# Ana-DigiColorMixerV1.net
KiCad netlist of a schematic drawn in EAGLE
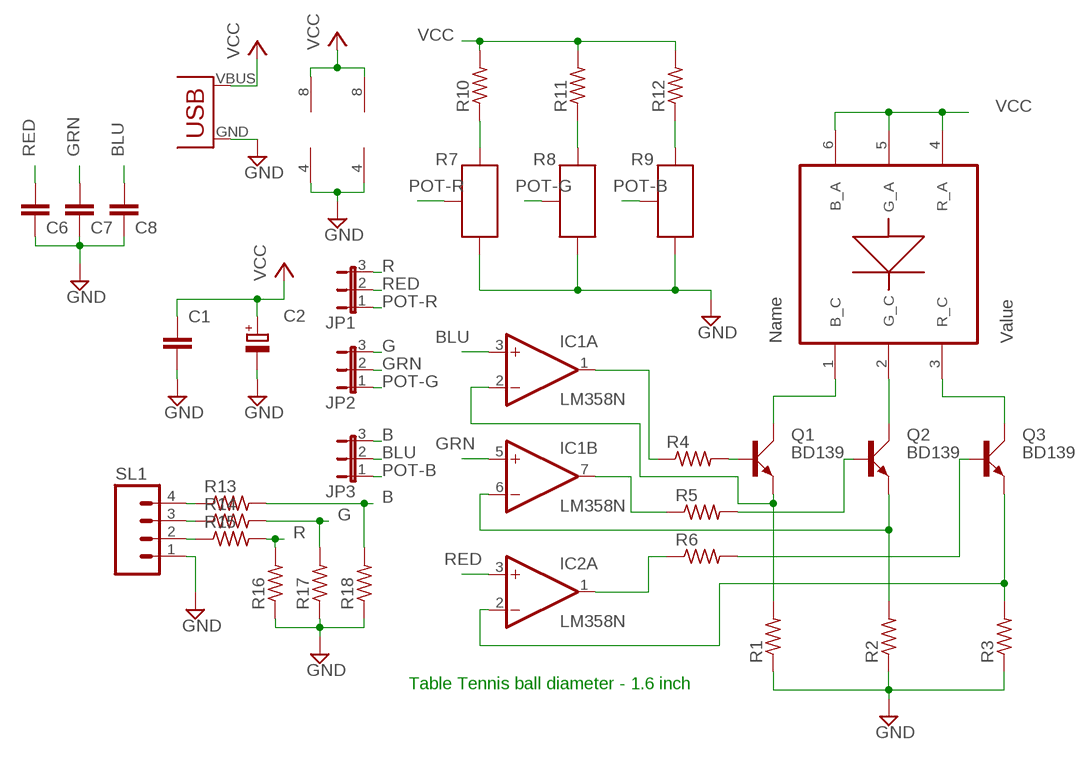
[diagram p0: schematic, sheet 1]

(export (version "E")
  (design (tool "Eeschema 10.0.6"))
  (components
    (comp (ref "C1")
      (value "0.1uf")
      (footprint "eagle-import:C025-024X044")
      (libsource (lib "eagle-import") (part "C-EU025-024X044"))
    )
    (comp (ref "C2")
      (value "100uf")
      (footprint "eagle-import:E3,5-8")
      (libsource (lib "eagle-import") (part "CPOL-EUE3.5-8"))
    )
    (comp (ref "C6")
      (value "0.1uf")
      (footprint "eagle-import:C025-024X044")
      (libsource (lib "eagle-import") (part "C-EU025-024X044"))
    )
    (comp (ref "C7")
      (value "0.1uf")
      (footprint "eagle-import:C025-024X044")
      (libsource (lib "eagle-import") (part "C-EU025-024X044"))
    )
    (comp (ref "C8")
      (value "0.1uf")
      (footprint "eagle-import:C025-024X044")
      (libsource (lib "eagle-import") (part "C-EU025-024X044"))
    )
    (comp (ref "IC1")
      (value "LM358N")
      (footprint "eagle-import:DIL08")
      (libsource (lib "eagle-import") (part "LM358N"))
    )
    (comp (ref "IC2")
      (value "LM358N")
      (footprint "eagle-import:DIL08")
      (libsource (lib "eagle-import") (part "LM358N"))
    )
    (comp (ref "JP1")
      (value "JP2E")
      (footprint "eagle-import:JP2")
      (libsource (lib "eagle-import") (part "JP2E"))
    )
    (comp (ref "JP2")
      (value "JP2E")
      (footprint "eagle-import:JP2")
      (libsource (lib "eagle-import") (part "JP2E"))
    )
    (comp (ref "JP3")
      (value "JP2E")
      (footprint "eagle-import:JP2")
      (libsource (lib "eagle-import") (part "JP2E"))
    )
    (comp (ref "Q1")
      (value "BD139")
      (footprint "eagle-import:TO126AV")
      (libsource (lib "eagle-import") (part "BD139"))
    )
    (comp (ref "Q2")
      (value "BD139")
      (footprint "eagle-import:TO126AV")
      (libsource (lib "eagle-import") (part "BD139"))
    )
    (comp (ref "Q3")
      (value "BD139")
      (footprint "eagle-import:TO126AV")
      (libsource (lib "eagle-import") (part "BD139"))
    )
    (comp (ref "R1")
      (value "4.7")
      (footprint "eagle-import:0411_15")
      (libsource (lib "eagle-import") (part "R-US_0411/15"))
    )
    (comp (ref "R2")
      (value "R-US_0411/15")
      (footprint "eagle-import:0411_15")
      (libsource (lib "eagle-import") (part "R-US_0411/15"))
    )
    (comp (ref "R3")
      (value "R-US_0411/15")
      (footprint "eagle-import:0411_15")
      (libsource (lib "eagle-import") (part "R-US_0411/15"))
    )
    (comp (ref "R4")
      (value "R-US_0204/7")
      (footprint "eagle-import:0204_7")
      (libsource (lib "eagle-import") (part "R-US_0204/7"))
    )
    (comp (ref "R5")
      (value "R-US_0204/7")
      (footprint "eagle-import:0204_7")
      (libsource (lib "eagle-import") (part "R-US_0204/7"))
    )
    (comp (ref "R6")
      (value "R-US_0204/7")
      (footprint "eagle-import:0204_7")
      (libsource (lib "eagle-import") (part "R-US_0204/7"))
    )
    (comp (ref "R7")
      (value "POTNORMAL")
      (footprint "eagle-import:RJ9W")
      (libsource (lib "eagle-import") (part "POTNORMAL"))
    )
    (comp (ref "R8")
      (value "POTNORMAL")
      (footprint "eagle-import:RJ9W")
      (libsource (lib "eagle-import") (part "POTNORMAL"))
    )
    (comp (ref "R9")
      (value "POTNORMAL")
      (footprint "eagle-import:RJ9W")
      (libsource (lib "eagle-import") (part "POTNORMAL"))
    )
    (comp (ref "R10")
      (value "R-US_0204/7")
      (footprint "eagle-import:0204_7")
      (libsource (lib "eagle-import") (part "R-US_0204/7"))
    )
    (comp (ref "R11")
      (value "R-US_0204/7")
      (footprint "eagle-import:0204_7")
      (libsource (lib "eagle-import") (part "R-US_0204/7"))
    )
    (comp (ref "R12")
      (value "R-US_0204/7")
      (footprint "eagle-import:0204_7")
      (libsource (lib "eagle-import") (part "R-US_0204/7"))
    )
    (comp (ref "R13")
      (value "R-US_0204/7")
      (footprint "eagle-import:0204_7")
      (libsource (lib "eagle-import") (part "R-US_0204/7"))
    )
    (comp (ref "R14")
      (value "R-US_0204/7")
      (footprint "eagle-import:0204_7")
      (libsource (lib "eagle-import") (part "R-US_0204/7"))
    )
    (comp (ref "R15")
      (value "R-US_0204/7")
      (footprint "eagle-import:0204_7")
      (libsource (lib "eagle-import") (part "R-US_0204/7"))
    )
    (comp (ref "R16")
      (value "R-US_0204/7")
      (footprint "eagle-import:0204_7")
      (libsource (lib "eagle-import") (part "R-US_0204/7"))
    )
    (comp (ref "R17")
      (value "R-US_0204/7")
      (footprint "eagle-import:0204_7")
      (libsource (lib "eagle-import") (part "R-US_0204/7"))
    )
    (comp (ref "R18")
      (value "R-US_0204/7")
      (footprint "eagle-import:0204_7")
      (libsource (lib "eagle-import") (part "R-US_0204/7"))
    )
    (comp (ref "SL1")
      (value "M04")
      (footprint "eagle-import:04P")
      (libsource (lib "eagle-import") (part "M04"))
    )
    (comp (ref "U$1")
      (value "RGB_SMD_3W")
      (footprint "eagle-import:RGB_SMD_6PIN")
      (libsource (lib "eagle-import") (part "RGB_SMD_3W"))
    )
    (comp (ref "U$2")
      (value "USB(POWER)")
      (footprint "eagle-import:USB(POWER)")
      (libsource (lib "eagle-import") (part "USB(POWER)"))
    )
  )
  (nets
    (net (code "1") (name "/B") (class "Default")
      (node (ref "JP3") (pin "3") (pinfunction "3_3") (pintype "passive"))
      (node (ref "R13") (pin "2") (pinfunction "2_2") (pintype "passive"))
      (node (ref "R18") (pin "2") (pinfunction "2_2") (pintype "passive"))
    )
    (net (code "2") (name "/BLU") (class "Default")
      (node (ref "C8") (pin "1") (pinfunction "1_1") (pintype "passive"))
      (node (ref "IC1") (pin "3") (pinfunction "+IN_3") (pintype "input"))
      (node (ref "JP3") (pin "2") (pinfunction "2_2") (pintype "passive"))
    )
    (net (code "3") (name "/G") (class "Default")
      (node (ref "JP2") (pin "3") (pinfunction "3_3") (pintype "passive"))
      (node (ref "R14") (pin "2") (pinfunction "2_2") (pintype "passive"))
      (node (ref "R17") (pin "2") (pinfunction "2_2") (pintype "passive"))
    )
    (net (code "4") (name "/GRN") (class "Default")
      (node (ref "C7") (pin "1") (pinfunction "1_1") (pintype "passive"))
      (node (ref "IC1") (pin "5") (pinfunction "+IN_5") (pintype "input"))
      (node (ref "JP2") (pin "2") (pinfunction "2_2") (pintype "passive"))
    )
    (net (code "5") (name "/POT-B") (class "Default")
      (node (ref "JP3") (pin "1") (pinfunction "1_1") (pintype "passive"))
      (node (ref "R9") (pin "S") (pinfunction "S_S") (pintype "passive"))
    )
    (net (code "6") (name "/POT-G") (class "Default")
      (node (ref "JP2") (pin "1") (pinfunction "1_1") (pintype "passive"))
      (node (ref "R8") (pin "S") (pinfunction "S_S") (pintype "passive"))
    )
    (net (code "7") (name "/POT-R") (class "Default")
      (node (ref "JP1") (pin "1") (pinfunction "1_1") (pintype "passive"))
      (node (ref "R7") (pin "S") (pinfunction "S_S") (pintype "passive"))
    )
    (net (code "8") (name "/R") (class "Default")
      (node (ref "JP1") (pin "3") (pinfunction "3_3") (pintype "passive"))
      (node (ref "R15") (pin "2") (pinfunction "2_2") (pintype "passive"))
      (node (ref "R16") (pin "2") (pinfunction "2_2") (pintype "passive"))
    )
    (net (code "9") (name "/RED") (class "Default")
      (node (ref "C6") (pin "1") (pinfunction "1_1") (pintype "passive"))
      (node (ref "IC2") (pin "3") (pinfunction "+IN_3") (pintype "input"))
      (node (ref "JP1") (pin "2") (pinfunction "2_2") (pintype "passive"))
    )
    (net (code "10") (name "GND") (class "Default")
      (node (ref "C1") (pin "2") (pinfunction "2_2") (pintype "passive"))
      (node (ref "C2") (pin "-") (pinfunction "-_-") (pintype "passive"))
      (node (ref "C6") (pin "2") (pinfunction "2_2") (pintype "passive"))
      (node (ref "C7") (pin "2") (pinfunction "2_2") (pintype "passive"))
      (node (ref "C8") (pin "2") (pinfunction "2_2") (pintype "passive"))
      (node (ref "IC1") (pin "4") (pinfunction "V-_4") (pintype "power_in"))
      (node (ref "IC2") (pin "4") (pinfunction "V-_4") (pintype "power_in"))
      (node (ref "R1") (pin "1") (pinfunction "1_1") (pintype "passive"))
      (node (ref "R16") (pin "1") (pinfunction "1_1") (pintype "passive"))
      (node (ref "R17") (pin "1") (pinfunction "1_1") (pintype "passive"))
      (node (ref "R18") (pin "1") (pinfunction "1_1") (pintype "passive"))
      (node (ref "R2") (pin "1") (pinfunction "1_1") (pintype "passive"))
      (node (ref "R3") (pin "1") (pinfunction "1_1") (pintype "passive"))
      (node (ref "R7") (pin "A") (pinfunction "A_A") (pintype "passive"))
      (node (ref "R8") (pin "A") (pinfunction "A_A") (pintype "passive"))
      (node (ref "R9") (pin "A") (pinfunction "A_A") (pintype "passive"))
      (node (ref "SL1") (pin "1") (pinfunction "1_1") (pintype "passive"))
      (node (ref "U$2") (pin "GND") (pinfunction "GND_GND") (pintype "power_in"))
    )
    (net (code "11") (name "Net-(IC1A--IN)") (class "Default")
      (node (ref "IC1") (pin "2") (pinfunction "-IN_2") (pintype "input"))
      (node (ref "Q1") (pin "E") (pinfunction "E_E") (pintype "passive"))
      (node (ref "R1") (pin "2") (pinfunction "2_2") (pintype "passive"))
    )
    (net (code "12") (name "Net-(IC1A-OUT)") (class "Default")
      (node (ref "IC1") (pin "1") (pinfunction "OUT_1") (pintype "output"))
      (node (ref "R4") (pin "1") (pinfunction "1_1") (pintype "passive"))
    )
    (net (code "13") (name "Net-(IC1B--IN)") (class "Default")
      (node (ref "IC1") (pin "6") (pinfunction "-IN_6") (pintype "input"))
      (node (ref "Q2") (pin "E") (pinfunction "E_E") (pintype "passive"))
      (node (ref "R2") (pin "2") (pinfunction "2_2") (pintype "passive"))
    )
    (net (code "14") (name "Net-(IC1B-OUT)") (class "Default")
      (node (ref "IC1") (pin "7") (pinfunction "OUT_7") (pintype "output"))
      (node (ref "R5") (pin "1") (pinfunction "1_1") (pintype "passive"))
    )
    (net (code "15") (name "Net-(IC2A--IN)") (class "Default")
      (node (ref "IC2") (pin "2") (pinfunction "-IN_2") (pintype "input"))
      (node (ref "Q3") (pin "E") (pinfunction "E_E") (pintype "passive"))
      (node (ref "R3") (pin "2") (pinfunction "2_2") (pintype "passive"))
    )
    (net (code "16") (name "Net-(IC2A-OUT)") (class "Default")
      (node (ref "IC2") (pin "1") (pinfunction "OUT_1") (pintype "output"))
      (node (ref "R6") (pin "1") (pinfunction "1_1") (pintype "passive"))
    )
    (net (code "17") (name "Net-(Q1-PadB)") (class "Default")
      (node (ref "Q1") (pin "B") (pinfunction "B_B") (pintype "passive"))
      (node (ref "R4") (pin "2") (pinfunction "2_2") (pintype "passive"))
    )
    (net (code "18") (name "Net-(Q2-PadB)") (class "Default")
      (node (ref "Q2") (pin "B") (pinfunction "B_B") (pintype "passive"))
      (node (ref "R5") (pin "2") (pinfunction "2_2") (pintype "passive"))
    )
    (net (code "19") (name "Net-(Q3-PadB)") (class "Default")
      (node (ref "Q3") (pin "B") (pinfunction "B_B") (pintype "passive"))
      (node (ref "R6") (pin "2") (pinfunction "2_2") (pintype "passive"))
    )
    (net (code "20") (name "Net-(R10-Pad1)") (class "Default")
      (node (ref "R10") (pin "1") (pinfunction "1_1") (pintype "passive"))
      (node (ref "R7") (pin "E") (pinfunction "E_E") (pintype "passive"))
    )
    (net (code "21") (name "Net-(R11-Pad1)") (class "Default")
      (node (ref "R11") (pin "1") (pinfunction "1_1") (pintype "passive"))
      (node (ref "R8") (pin "E") (pinfunction "E_E") (pintype "passive"))
    )
    (net (code "22") (name "Net-(R12-Pad1)") (class "Default")
      (node (ref "R12") (pin "1") (pinfunction "1_1") (pintype "passive"))
      (node (ref "R9") (pin "E") (pinfunction "E_E") (pintype "passive"))
    )
    (net (code "23") (name "Net-(R13-Pad1)") (class "Default")
      (node (ref "R13") (pin "1") (pinfunction "1_1") (pintype "passive"))
      (node (ref "SL1") (pin "4") (pinfunction "4_4") (pintype "passive"))
    )
    (net (code "24") (name "Net-(R14-Pad1)") (class "Default")
      (node (ref "R14") (pin "1") (pinfunction "1_1") (pintype "passive"))
      (node (ref "SL1") (pin "3") (pinfunction "3_3") (pintype "passive"))
    )
    (net (code "25") (name "Net-(R15-Pad1)") (class "Default")
      (node (ref "R15") (pin "1") (pinfunction "1_1") (pintype "passive"))
      (node (ref "SL1") (pin "2") (pinfunction "2_2") (pintype "passive"))
    )
    (net (code "26") (name "Net-(U$1-B_C)") (class "Default")
      (node (ref "Q1") (pin "C") (pinfunction "C_C") (pintype "passive"))
      (node (ref "U$1") (pin "1") (pinfunction "B_C_1") (pintype "passive"))
    )
    (net (code "27") (name "Net-(U$1-G_C)") (class "Default")
      (node (ref "Q2") (pin "C") (pinfunction "C_C") (pintype "passive"))
      (node (ref "U$1") (pin "2") (pinfunction "G_C_2") (pintype "passive"))
    )
    (net (code "28") (name "Net-(U$1-R_C)") (class "Default")
      (node (ref "Q3") (pin "C") (pinfunction "C_C") (pintype "passive"))
      (node (ref "U$1") (pin "3") (pinfunction "R_C_3") (pintype "passive"))
    )
    (net (code "29") (name "VCC") (class "Default")
      (node (ref "C1") (pin "1") (pinfunction "1_1") (pintype "passive"))
      (node (ref "C2") (pin "+") (pinfunction "+_+") (pintype "passive"))
      (node (ref "IC1") (pin "8") (pinfunction "V+_8") (pintype "power_in"))
      (node (ref "IC2") (pin "8") (pinfunction "V+_8") (pintype "power_in"))
      (node (ref "R10") (pin "2") (pinfunction "2_2") (pintype "passive"))
      (node (ref "R11") (pin "2") (pinfunction "2_2") (pintype "passive"))
      (node (ref "R12") (pin "2") (pinfunction "2_2") (pintype "passive"))
      (node (ref "U$1") (pin "4") (pinfunction "R_A_4") (pintype "passive"))
      (node (ref "U$1") (pin "5") (pinfunction "G_A_5") (pintype "passive"))
      (node (ref "U$1") (pin "6") (pinfunction "B_A_6") (pintype "passive"))
      (node (ref "U$2") (pin "VBUS") (pinfunction "VCC_VBUS") (pintype "power_in"))
    )
  )
)
